# 3V0_reference.net
KiCad netlist of a schematic drawn in Altium Designer
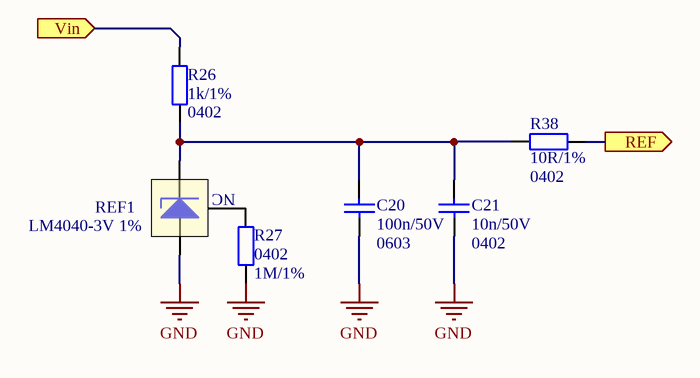
[diagram p0: 3V0_reference.SchDoc]

(export (version "E")
  (design (tool "Eeschema 10.0.6"))
  (components
    (comp (ref "C20")
      (value "100n/50V")
      (footprint "SMD_Capacitor_0603")
      (description "Ceramic Cap Kemet COTS 100n/50V X7R 0603")
      (fields
        (field (name "MANUFACTURER") "Kemet")
        (field (name "MANUFACTURERPARTNUMBER") "C0603T104K5RALTU")
        (field (name "PACKAGE") "0603")
      )
      (libsource (lib "capacitors") (part "Cer_C0603T104K5RALTU"))
    )
    (comp (ref "C21")
      (value "10n/50V")
      (footprint "SMD_Capacitor_0402")
      (description "Ceramic Cap Kemet COTS 10n/50V X7R 0402")
      (fields
        (field (name "MANUFACTURERPARTNUMBER") "C0402T103K5RALTU")
        (field (name "MANUFACTURER") "Kemet")
        (field (name "PACKAGE") "0402")
      )
      (libsource (lib "capacitors") (part "Cer_C0402T103K5RALTU"))
    )
    (comp (ref "R26")
      (value "1k/1%")
      (footprint "SMD_Resistor_0402")
      (description "1k/1% Vishay CRCW 0402 Resistor. 63mW, 100ppm, 50V.")
      (fields
        (field (name "MANUFACTURER") "Vishay")
        (field (name "MANUFACTURERPARTNUMBER") "CRCW04021K00FKxxxx")
        (field (name "PACKAGE") "0402")
      )
      (libsource (lib "resistors") (part "CRCW04021K00FKxxxx"))
    )
    (comp (ref "R27")
      (value "1M/1%")
      (footprint "SMD_Resistor_0402")
      (description "1M/1% Vishay CRCW 0402 Resistor. 63mW, 100ppm, 50V.")
      (fields
        (field (name "MANUFACTURER") "Vishay")
        (field (name "MANUFACTURERPARTNUMBER") "CRCW04021M00FKxxxx")
        (field (name "PACKAGE") "0402")
      )
      (libsource (lib "resistors") (part "CRCW04021M00FKxxxx"))
    )
    (comp (ref "R38")
      (value "10R/1%")
      (footprint "SMD_Resistor_0402")
      (description "10R/1% Vishay CRCW 0402 Resistor. 63mW, 100ppm, 50V.")
      (fields
        (field (name "MANUFACTURER") "Vishay")
        (field (name "MANUFACTURERPARTNUMBER") "CRCW040210R0FKxxxx")
        (field (name "PACKAGE") "0402")
      )
      (libsource (lib "resistors") (part "CRCW040210R0FKxxxx"))
    )
    (comp (ref "REF1")
      (value "LM4040-3V 1%")
      (footprint "SOT23-3")
      (description "Shunt V-REF, 3V, 1%, SOT23-3")
      (fields
        (field (name "MANUFACTURERPARTNUMBER") "LM4040DIM3-3.0")
        (field (name "MANUFACTURER") "Texas Instruments")
      )
      (libsource (lib "diodes") (part "LM4040DIM3-3.0"))
    )
  )
  (nets
    (net (code "1") (name "/REF") (class "Default")
      (node (ref "R38") (pin "2") (pinfunction "2_2") (pintype "passive"))
    )
    (net (code "2") (name "/Vin") (class "Default")
      (node (ref "R26") (pin "1") (pinfunction "1_1") (pintype "passive"))
    )
    (net (code "3") (name "GND") (class "Default")
      (node (ref "C20") (pin "2") (pinfunction "2_2") (pintype "passive"))
      (node (ref "C21") (pin "2") (pinfunction "2_2") (pintype "passive"))
      (node (ref "R27") (pin "2") (pinfunction "2_2") (pintype "passive"))
      (node (ref "REF1") (pin "2") (pinfunction "A_2") (pintype "passive"))
    )
    (net (code "4") (name "Net-(REF1-K)") (class "Default")
      (node (ref "C20") (pin "1") (pinfunction "1_1") (pintype "passive"))
      (node (ref "C21") (pin "1") (pinfunction "1_1") (pintype "passive"))
      (node (ref "R26") (pin "2") (pinfunction "2_2") (pintype "passive"))
      (node (ref "R38") (pin "1") (pinfunction "1_1") (pintype "passive"))
      (node (ref "REF1") (pin "1") (pinfunction "K_1") (pintype "passive"))
    )
    (net (code "5") (name "Net-(REF1-NC)") (class "Default")
      (node (ref "R27") (pin "1") (pinfunction "1_1") (pintype "passive"))
      (node (ref "REF1") (pin "3") (pinfunction "NC_3") (pintype "passive"))
    )
  )
)
